# mainboard_interface_v1_0.net
KiCad netlist of a schematic drawn in Altium Designer
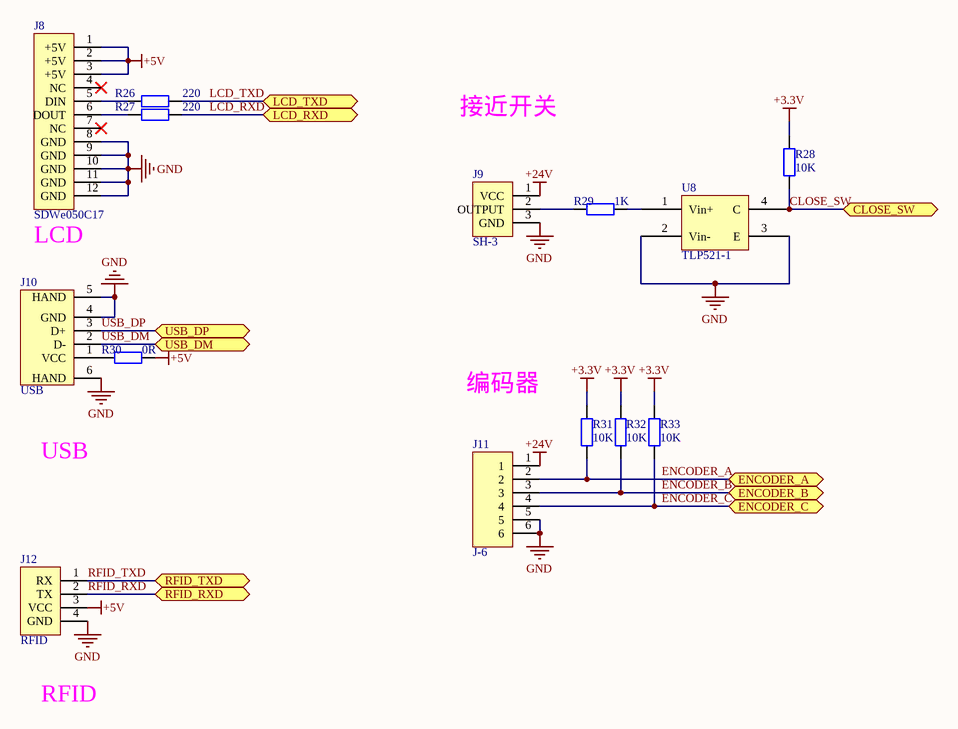
[diagram p0: mainboard_interface.v1.0.SchDoc]

(export (version "E")
  (design (tool "Eeschema 10.0.6"))
  (components
    (comp (ref "J8")
      (value "SDWe050C17")
      (footprint "FCC1.0-10")
      (libsource (lib "Connector") (part "SH-12"))
    )
    (comp (ref "J9") (value "SH-3") (footprint "PH2.0-3T") (libsource (lib "Connector") (part "SH-3")))
    (comp (ref "J10") (value "USB") (footprint "USB_FEMALE_A") (libsource (lib "Connector") (part "USB")))
    (comp (ref "J11") (value "J-6") (footprint "PH2.0-6P") (libsource (lib "Connector") (part "SH-6")))
    (comp (ref "J12") (value "RFID") (footprint "J254-4") (libsource (lib "Connector") (part "SH-4")))
    (comp (ref "R26")
      (value "220")
      (footprint "0805")
      (description "Resistor")
      (fields (field (name "PUBLISHER") "Altium Limited"))
      (libsource (lib "") (part "Res2_2"))
    )
    (comp (ref "R27")
      (value "220")
      (footprint "0805")
      (description "Resistor")
      (fields (field (name "PUBLISHER") "Altium Limited"))
      (libsource (lib "") (part "Res2_2"))
    )
    (comp (ref "R28")
      (value "10K")
      (footprint "0805")
      (description "Resistor")
      (fields (field (name "PUBLISHER") "Altium Limited"))
      (libsource (lib "") (part "Res2_1"))
    )
    (comp (ref "R29")
      (value "1K")
      (footprint "0805")
      (description "Resistor")
      (fields (field (name "PUBLISHER") "Altium Limited"))
      (libsource (lib "TIAN's Schlib") (part "Res2"))
    )
    (comp (ref "R30")
      (value "0R")
      (footprint "0805")
      (description "Resistor")
      (fields (field (name "PUBLISHER") "Altium Limited"))
      (libsource (lib "TIAN's Schlib") (part "Res2"))
    )
    (comp (ref "R31")
      (value "10K")
      (footprint "0805")
      (description "Resistor")
      (fields (field (name "PUBLISHER") "Altium Limited"))
      (libsource (lib "") (part "Res2_1"))
    )
    (comp (ref "R32")
      (value "10K")
      (footprint "0805")
      (description "Resistor")
      (fields (field (name "PUBLISHER") "Altium Limited"))
      (libsource (lib "") (part "Res2_1"))
    )
    (comp (ref "R33")
      (value "10K")
      (footprint "0805")
      (description "Resistor")
      (fields (field (name "PUBLISHER") "Altium Limited"))
      (libsource (lib "") (part "Res2_1"))
    )
    (comp (ref "U8") (value "TLP521-1") (footprint "DIP-4") (libsource (lib "Chip") (part "TLP521-1")))
  )
  (nets
    (net (code "1") (name "+3.3V") (class "Default")
      (node (ref "R28") (pin "1") (pinfunction "1_1") (pintype "passive"))
      (node (ref "R31") (pin "1") (pinfunction "1_1") (pintype "passive"))
      (node (ref "R32") (pin "1") (pinfunction "1_1") (pintype "passive"))
      (node (ref "R33") (pin "1") (pinfunction "1_1") (pintype "passive"))
    )
    (net (code "2") (name "+5V") (class "Default")
      (node (ref "J12") (pin "3") (pinfunction "VCC_3") (pintype "passive"))
      (node (ref "J8") (pin "1") (pinfunction "+5V_1") (pintype "passive"))
      (node (ref "J8") (pin "2") (pinfunction "+5V_2") (pintype "passive"))
      (node (ref "J8") (pin "3") (pinfunction "+5V_3") (pintype "passive"))
      (node (ref "R30") (pin "1") (pinfunction "1_1") (pintype "passive"))
    )
    (net (code "3") (name "+24V") (class "Default")
      (node (ref "J11") (pin "1") (pinfunction "1_1") (pintype "passive"))
      (node (ref "J9") (pin "1") (pinfunction "VCC_1") (pintype "passive"))
    )
    (net (code "4") (name "/CLOSE_SW") (class "Default")
      (node (ref "R28") (pin "2") (pinfunction "2_2") (pintype "passive"))
      (node (ref "U8") (pin "4") (pinfunction "C_4") (pintype "passive"))
    )
    (net (code "5") (name "/ENCODER_A") (class "Default")
      (node (ref "J11") (pin "2") (pinfunction "2_2") (pintype "passive"))
      (node (ref "R31") (pin "2") (pinfunction "2_2") (pintype "passive"))
    )
    (net (code "6") (name "/ENCODER_B") (class "Default")
      (node (ref "J11") (pin "3") (pinfunction "3_3") (pintype "passive"))
      (node (ref "R32") (pin "2") (pinfunction "2_2") (pintype "passive"))
    )
    (net (code "7") (name "/ENCODER_C") (class "Default")
      (node (ref "J11") (pin "4") (pinfunction "4_4") (pintype "passive"))
      (node (ref "R33") (pin "2") (pinfunction "2_2") (pintype "passive"))
    )
    (net (code "8") (name "/LCD_RXD") (class "Default")
      (node (ref "R27") (pin "2") (pinfunction "2_2") (pintype "passive"))
    )
    (net (code "9") (name "/LCD_TXD") (class "Default")
      (node (ref "R26") (pin "2") (pinfunction "2_2") (pintype "passive"))
    )
    (net (code "10") (name "/RFID_RXD") (class "Default")
      (node (ref "J12") (pin "2") (pinfunction "TX_2") (pintype "passive"))
    )
    (net (code "11") (name "/RFID_TXD") (class "Default")
      (node (ref "J12") (pin "1") (pinfunction "RX_1") (pintype "passive"))
    )
    (net (code "12") (name "/USB_DM") (class "Default")
      (node (ref "J10") (pin "2") (pinfunction "D-_2") (pintype "passive"))
    )
    (net (code "13") (name "/USB_DP") (class "Default")
      (node (ref "J10") (pin "3") (pinfunction "D+_3") (pintype "passive"))
    )
    (net (code "14") (name "GND") (class "Default")
      (node (ref "J10") (pin "4") (pinfunction "GND_4") (pintype "passive"))
      (node (ref "J10") (pin "5") (pinfunction "HAND_5") (pintype "passive"))
      (node (ref "J10") (pin "6") (pinfunction "HAND_6") (pintype "passive"))
      (node (ref "J11") (pin "5") (pinfunction "5_5") (pintype "passive"))
      (node (ref "J11") (pin "6") (pinfunction "6_6") (pintype "passive"))
      (node (ref "J12") (pin "4") (pinfunction "GND_4") (pintype "passive"))
      (node (ref "J8") (pin "10") (pinfunction "GND_10") (pintype "passive"))
      (node (ref "J8") (pin "11") (pinfunction "GND_11") (pintype "passive"))
      (node (ref "J8") (pin "12") (pinfunction "GND_12") (pintype "passive"))
      (node (ref "J8") (pin "8") (pinfunction "GND_8") (pintype "passive"))
      (node (ref "J8") (pin "9") (pinfunction "GND_9") (pintype "passive"))
      (node (ref "J9") (pin "3") (pinfunction "GND_3") (pintype "passive"))
      (node (ref "U8") (pin "2") (pinfunction "Vin-_2") (pintype "passive"))
      (node (ref "U8") (pin "3") (pinfunction "E_3") (pintype "passive"))
    )
    (net (code "15") (name "Net-(J8-DIN)") (class "Default")
      (node (ref "J8") (pin "5") (pinfunction "DIN_5") (pintype "passive"))
      (node (ref "R26") (pin "1") (pinfunction "1_1") (pintype "passive"))
    )
    (net (code "16") (name "Net-(J8-DOUT)") (class "Default")
      (node (ref "J8") (pin "6") (pinfunction "DOUT_6") (pintype "passive"))
      (node (ref "R27") (pin "1") (pinfunction "1_1") (pintype "passive"))
    )
    (net (code "17") (name "Net-(J9-OUTPUT)") (class "Default")
      (node (ref "J9") (pin "2") (pinfunction "OUTPUT_2") (pintype "passive"))
      (node (ref "R29") (pin "2") (pinfunction "2_2") (pintype "passive"))
    )
    (net (code "18") (name "Net-(J10-VCC)") (class "Default")
      (node (ref "J10") (pin "1") (pinfunction "VCC_1") (pintype "passive"))
      (node (ref "R30") (pin "2") (pinfunction "2_2") (pintype "passive"))
    )
    (net (code "19") (name "Net-(U8-Vin+)") (class "Default")
      (node (ref "R29") (pin "1") (pinfunction "1_1") (pintype "passive"))
      (node (ref "U8") (pin "1") (pinfunction "Vin+_1") (pintype "passive"))
    )
    (net (code "20") (name "unconnected-(J8-NC-Pad4)") (class "Default")
      (node (ref "J8") (pin "4") (pinfunction "NC_4") (pintype "passive+no_connect"))
    )
    (net (code "21") (name "unconnected-(J8-NC-Pad7)") (class "Default")
      (node (ref "J8") (pin "7") (pinfunction "NC_7") (pintype "passive+no_connect"))
    )
  )
)
